# Y.net
KiCad netlist of a schematic drawn in EAGLE
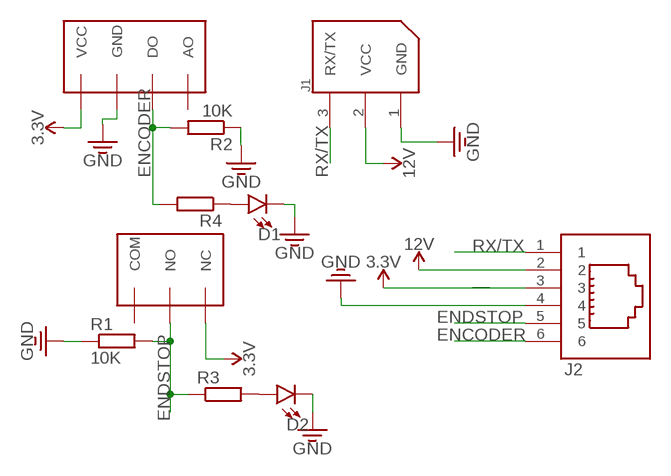
[diagram p0: schematic, sheet 1]

(export (version "E")
  (design (tool "Eeschema 10.0.6"))
  (components
    (comp (ref "D1")
      (value "LED5MM")
      (footprint "eagle-import:LED_5MM")
      (libsource (lib "eagle-import") (part "LED5MM"))
    )
    (comp (ref "D2")
      (value "LED5MM")
      (footprint "eagle-import:LED_5MM")
      (libsource (lib "eagle-import") (part "LED5MM"))
    )
    (comp (ref "J1")
      (value "22-03-5035")
      (footprint "eagle-import:5267-3")
      (libsource (lib "eagle-import") (part "22-03-5035"))
    )
    (comp (ref "J2")
      (value "615006138421")
      (footprint "eagle-import:615006138421")
      (libsource (lib "eagle-import") (part "615006138421"))
    )
    (comp (ref "R1")
      (value "10K")
      (footprint "eagle-import:0204_7")
      (libsource (lib "eagle-import") (part "R-EU_0204/7"))
    )
    (comp (ref "R2")
      (value "10K")
      (footprint "eagle-import:0204_7")
      (libsource (lib "eagle-import") (part "R-EU_0204/7"))
    )
    (comp (ref "R3")
      (value "R-EU_0204/7")
      (footprint "eagle-import:0204_7")
      (libsource (lib "eagle-import") (part "R-EU_0204/7"))
    )
    (comp (ref "R4")
      (value "R-EU_0204/7")
      (footprint "eagle-import:0204_7")
      (libsource (lib "eagle-import") (part "R-EU_0204/7"))
    )
    (comp (ref "U$1")
      (value "OPTICAL_ENCODER_FC-01")
      (footprint "eagle-import:OPTICAL_ENCODER_FC-01")
      (libsource (lib "eagle-import") (part "OPTICAL_ENCODER_FC-01"))
    )
    (comp (ref "U$2")
      (value "ENDSTOP")
      (footprint "eagle-import:ENDSTOP")
      (libsource (lib "eagle-import") (part "ENDSTOP"))
    )
  )
  (nets
    (net (code "1") (name "/ENCODER") (class "Default")
      (node (ref "J2") (pin "6") (pinfunction "6_6") (pintype "passive"))
      (node (ref "R2") (pin "2") (pinfunction "2_2") (pintype "passive"))
      (node (ref "R4") (pin "2") (pinfunction "2_2") (pintype "passive"))
      (node (ref "U$1") (pin "DO") (pinfunction "DO_DO") (pintype "bidirectional"))
    )
    (net (code "2") (name "/ENDSTOP") (class "Default")
      (node (ref "J2") (pin "5") (pinfunction "5_5") (pintype "passive"))
      (node (ref "R1") (pin "2") (pinfunction "2_2") (pintype "passive"))
      (node (ref "R3") (pin "1") (pinfunction "1_1") (pintype "passive"))
      (node (ref "U$2") (pin "NO") (pinfunction "NO_NO") (pintype "bidirectional"))
    )
    (net (code "3") (name "/RX{slash}TX") (class "Default")
      (node (ref "J1") (pin "3") (pinfunction "RX/TX_3") (pintype "bidirectional"))
      (node (ref "J2") (pin "1") (pinfunction "1_1") (pintype "passive"))
    )
    (net (code "4") (name "3.3V") (class "Default")
      (node (ref "J2") (pin "3") (pinfunction "3_3") (pintype "passive"))
      (node (ref "U$1") (pin "VCC") (pinfunction "VCC_VCC") (pintype "bidirectional"))
      (node (ref "U$2") (pin "NC") (pinfunction "NC_NC") (pintype "bidirectional"))
    )
    (net (code "5") (name "12V") (class "Default")
      (node (ref "J1") (pin "2") (pinfunction "VCC_2") (pintype "bidirectional"))
      (node (ref "J2") (pin "2") (pinfunction "2_2") (pintype "passive"))
    )
    (net (code "6") (name "GND") (class "Default")
      (node (ref "D1") (pin "K") (pinfunction "C_K") (pintype "passive"))
      (node (ref "D2") (pin "K") (pinfunction "C_K") (pintype "passive"))
      (node (ref "J1") (pin "1") (pinfunction "GND_1") (pintype "bidirectional"))
      (node (ref "J2") (pin "4") (pinfunction "4_4") (pintype "passive"))
      (node (ref "R1") (pin "1") (pinfunction "1_1") (pintype "passive"))
      (node (ref "R2") (pin "1") (pinfunction "1_1") (pintype "passive"))
      (node (ref "U$1") (pin "GND") (pinfunction "GND_GND") (pintype "bidirectional"))
    )
    (net (code "7") (name "Net-(D1-PadA)") (class "Default")
      (node (ref "D1") (pin "A") (pinfunction "A_A") (pintype "passive"))
      (node (ref "R4") (pin "1") (pinfunction "1_1") (pintype "passive"))
    )
    (net (code "8") (name "Net-(D2-PadA)") (class "Default")
      (node (ref "D2") (pin "A") (pinfunction "A_A") (pintype "passive"))
      (node (ref "R3") (pin "2") (pinfunction "2_2") (pintype "passive"))
    )
    (net (code "9") (name "unconnected-(U$1-PadAO)") (class "Default")
      (node (ref "U$1") (pin "AO") (pinfunction "AO_AO") (pintype "bidirectional"))
    )
    (net (code "10") (name "unconnected-(U$2-PadCOM)") (class "Default")
      (node (ref "U$2") (pin "COM") (pinfunction "COM_COM") (pintype "bidirectional"))
    )
  )
)
